# ADC.net
KiCad netlist of a schematic drawn in Altium Designer
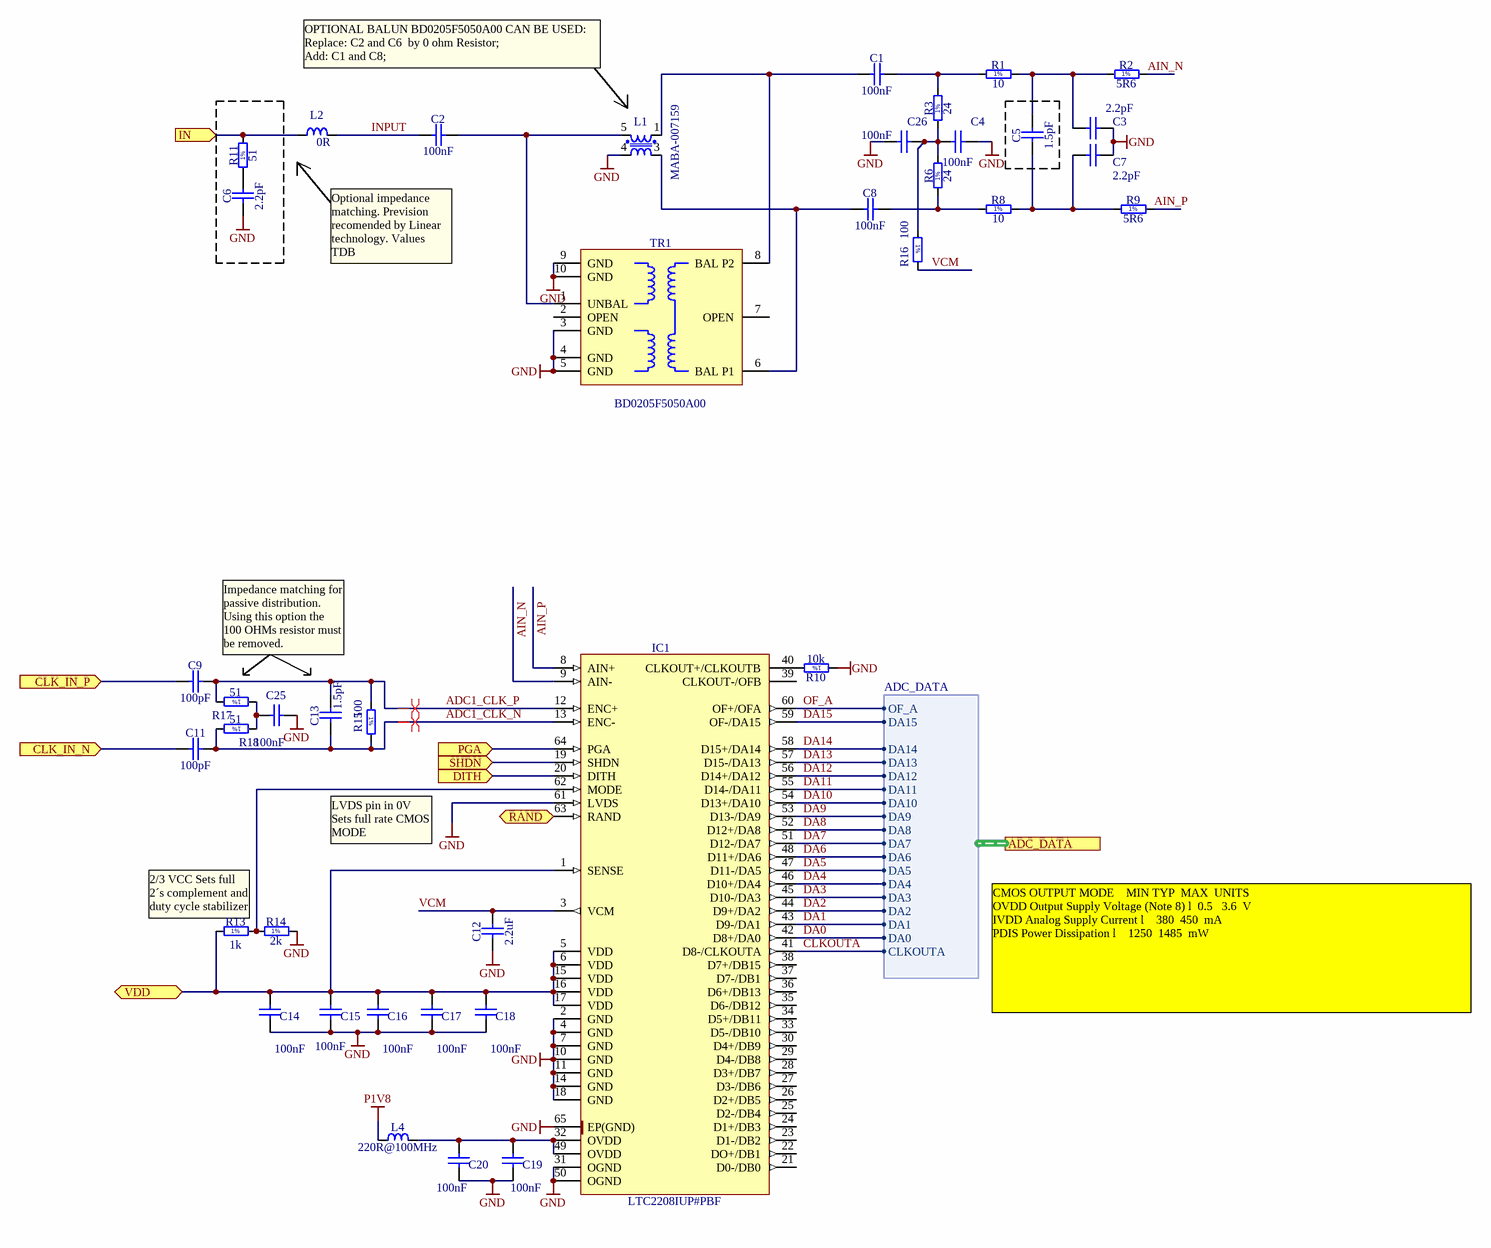
[diagram p0: ADC.SchDoc]

(export (version "E")
  (design (tool "Eeschema 10.0.6"))
  (components
    (comp (ref "C1")
      (value "100nF")
      (footprint "CAPC0603X33N")
      (description "Non-polarised capacitor")
      (fields
        (field (name "PART NUMBER") "CC0201_100NF_6.3V_10%_X5R")
        (field (name "VOLTAGE") "6.3V")
        (field (name "AUTHOR") "CERN DEM JLC")
      )
      (libsource (lib "Capacitors") (part "Capacitor - non polarized"))
    )
    (comp (ref "C2")
      (value "100nF")
      (footprint "CAPC0603X33N")
      (description "Non-polarised capacitor")
      (fields
        (field (name "PART NUMBER") "CC0201_100NF_6.3V_10%_X5R")
        (field (name "VOLTAGE") "6.3V")
        (field (name "AUTHOR") "CERN DEM JLC")
      )
      (libsource (lib "Capacitors") (part "Capacitor - non polarized"))
    )
    (comp (ref "C3")
      (value "2.2pF")
      (footprint "CAPC1005X55N")
      (description "Non-polarised capacitor")
      (fields
        (field (name "PART NUMBER") "CC0402_2.2PF_50V_0.25PF_NP0")
        (field (name "VOLTAGE") "50V")
        (field (name "AUTHOR") "CERN DEM JLC")
      )
      (libsource (lib "Capacitors") (part "Capacitor - non polarized"))
    )
    (comp (ref "C4")
      (value "100nF")
      (footprint "CAPC0603X33N")
      (description "Non-polarised capacitor")
      (fields
        (field (name "PART NUMBER") "CC0201_100NF_6.3V_10%_X5R")
        (field (name "VOLTAGE") "6.3V")
        (field (name "AUTHOR") "CERN DEM JLC")
      )
      (libsource (lib "Capacitors") (part "Capacitor - non polarized"))
    )
    (comp (ref "C5")
      (value "1.5pF")
      (footprint "CAPC1005X55N")
      (description "Non-polarised capacitor")
      (fields
        (field (name "PART NUMBER") "CC0402_1.5PF_50V_0.25PF_NP0")
        (field (name "VOLTAGE") "50V")
        (field (name "AUTHOR") "CERN DEM JLC")
      )
      (libsource (lib "Capacitors") (part "Capacitor - non polarized"))
    )
    (comp (ref "C6")
      (value "2.2pF")
      (footprint "CAPC1005X55N")
      (description "Non-polarised capacitor")
      (fields
        (field (name "PART NUMBER") "CC0402_2.2PF_50V_0.25PF_NP0")
        (field (name "VOLTAGE") "50V")
        (field (name "AUTHOR") "CERN DEM JLC")
      )
      (libsource (lib "Capacitors") (part "Capacitor - non polarized"))
    )
    (comp (ref "C7")
      (value "2.2pF")
      (footprint "CAPC1005X55N")
      (description "Non-polarised capacitor")
      (fields
        (field (name "PART NUMBER") "CC0402_2.2PF_50V_0.25PF_NP0")
        (field (name "VOLTAGE") "50V")
        (field (name "AUTHOR") "CERN DEM JLC")
      )
      (libsource (lib "Capacitors") (part "Capacitor - non polarized"))
    )
    (comp (ref "C8")
      (value "100nF")
      (footprint "CAPC0603X33N")
      (description "Non-polarised capacitor")
      (fields
        (field (name "PART NUMBER") "CC0201_100NF_6.3V_10%_X5R")
        (field (name "VOLTAGE") "6.3V")
        (field (name "AUTHOR") "CERN DEM JLC")
      )
      (libsource (lib "Capacitors") (part "Capacitor - non polarized"))
    )
    (comp (ref "C9")
      (value "100pF")
      (footprint "CAPC1005X55N")
      (description "Non-polarised capacitor")
      (fields
        (field (name "PART NUMBER") "CC0402_100PF_50V_5%_NP0")
        (field (name "VOLTAGE") "50V")
        (field (name "AUTHOR") "CERN DEM JLC")
      )
      (libsource (lib "Capacitors") (part "Capacitor - non polarized"))
    )
    (comp (ref "C11")
      (value "100pF")
      (footprint "CAPC1005X55N")
      (description "Non-polarised capacitor")
      (fields
        (field (name "PART NUMBER") "CC0402_100PF_50V_5%_NP0")
        (field (name "VOLTAGE") "50V")
        (field (name "AUTHOR") "CERN DEM JLC")
      )
      (libsource (lib "Capacitors") (part "Capacitor - non polarized"))
    )
    (comp (ref "C12")
      (value "2.2uF")
      (footprint "CAPC1608X87N")
      (description "Non-polarised capacitor")
      (fields
        (field (name "PART NUMBER") "CC0603_2.2UF_16V_10%_X5R")
        (field (name "VOLTAGE") "16V")
        (field (name "AUTHOR") "CERN DEM JLC")
      )
      (libsource (lib "Capacitors") (part "Capacitor - non polarized"))
    )
    (comp (ref "C13")
      (value "1.5pF")
      (footprint "CAPC1005X55N")
      (description "Non-polarised capacitor")
      (fields
        (field (name "PART NUMBER") "CC0402_1.5PF_50V_0.25PF_NP0")
        (field (name "VOLTAGE") "50V")
        (field (name "AUTHOR") "CERN DEM JLC")
      )
      (libsource (lib "Capacitors") (part "Capacitor - non polarized"))
    )
    (comp (ref "C14")
      (value "100nF")
      (footprint "CAPC0603X33N")
      (description "Non-polarised capacitor")
      (fields
        (field (name "PART NUMBER") "CC0201_100NF_6.3V_10%_X5R")
        (field (name "VOLTAGE") "6.3V")
        (field (name "AUTHOR") "CERN DEM JLC")
      )
      (libsource (lib "Capacitors") (part "Capacitor - non polarized"))
    )
    (comp (ref "C15")
      (value "100nF")
      (footprint "CAPC0603X33N")
      (description "Non-polarised capacitor")
      (fields
        (field (name "PART NUMBER") "CC0201_100NF_6.3V_10%_X5R")
        (field (name "VOLTAGE") "6.3V")
        (field (name "AUTHOR") "CERN DEM JLC")
      )
      (libsource (lib "Capacitors") (part "Capacitor - non polarized"))
    )
    (comp (ref "C16")
      (value "100nF")
      (footprint "CAPC0603X33N")
      (description "Non-polarised capacitor")
      (fields
        (field (name "PART NUMBER") "CC0201_100NF_6.3V_10%_X5R")
        (field (name "VOLTAGE") "6.3V")
        (field (name "AUTHOR") "CERN DEM JLC")
      )
      (libsource (lib "Capacitors") (part "Capacitor - non polarized"))
    )
    (comp (ref "C17")
      (value "100nF")
      (footprint "CAPC0603X33N")
      (description "Non-polarised capacitor")
      (fields
        (field (name "PART NUMBER") "CC0201_100NF_6.3V_10%_X5R")
        (field (name "VOLTAGE") "6.3V")
        (field (name "AUTHOR") "CERN DEM JLC")
      )
      (libsource (lib "Capacitors") (part "Capacitor - non polarized"))
    )
    (comp (ref "C18")
      (value "100nF")
      (footprint "CAPC0603X33N")
      (description "Non-polarised capacitor")
      (fields
        (field (name "PART NUMBER") "CC0201_100NF_6.3V_10%_X5R")
        (field (name "VOLTAGE") "6.3V")
        (field (name "AUTHOR") "CERN DEM JLC")
      )
      (libsource (lib "Capacitors") (part "Capacitor - non polarized"))
    )
    (comp (ref "C19")
      (value "100nF")
      (footprint "CAPC0603X33N")
      (description "Non-polarised capacitor")
      (fields
        (field (name "PART NUMBER") "CC0201_100NF_6.3V_10%_X5R")
        (field (name "VOLTAGE") "6.3V")
        (field (name "AUTHOR") "CERN DEM JLC")
      )
      (libsource (lib "Capacitors") (part "Capacitor - non polarized"))
    )
    (comp (ref "C20")
      (value "100nF")
      (footprint "CAPC0603X33N")
      (description "Non-polarised capacitor")
      (fields
        (field (name "PART NUMBER") "CC0201_100NF_6.3V_10%_X5R")
        (field (name "VOLTAGE") "6.3V")
        (field (name "AUTHOR") "CERN DEM JLC")
      )
      (libsource (lib "Capacitors") (part "Capacitor - non polarized"))
    )
    (comp (ref "C25")
      (value "100nF")
      (footprint "CAPC0603X33N")
      (description "Non-polarised capacitor")
      (fields
        (field (name "PART NUMBER") "CC0201_100NF_6.3V_10%_X5R")
        (field (name "VOLTAGE") "6.3V")
        (field (name "AUTHOR") "CERN DEM JLC")
      )
      (libsource (lib "Capacitors") (part "Capacitor - non polarized"))
    )
    (comp (ref "C26")
      (value "100nF")
      (footprint "CAPC0603X33N")
      (description "Non-polarised capacitor")
      (fields
        (field (name "PART NUMBER") "CC0201_100NF_6.3V_10%_X5R")
        (field (name "VOLTAGE") "6.3V")
        (field (name "AUTHOR") "CERN DEM JLC")
      )
      (libsource (lib "Capacitors") (part "Capacitor - non polarized"))
    )
    (comp (ref "IC1")
      (value "LTC2208IUP#PBF")
      (footprint "QFN50P900X900X80-65N-S725")
      (description "16-Bit, 130Msps ADC")
      (fields
        (field (name "PART NUMBER") "LTC2LTC2208IUP#PBF")
        (field (name "MANUFACTURER") "LINEAR TECHNOLOGY")
        (field (name "AUTHOR") "CERN DEM JLC")
      )
      (libsource (lib "ICs And Semiconductors") (part "LTC2208"))
    )
    (comp (ref "L1")
      (value "MABA-007159")
      (footprint "XFMR_MA-COM_SM-22 (H260)")
      (description "MA-COM E-Serie RF 1:1 Transmission Line Ttransformer 4.5-3000MHz")
      (libsource (lib "fmclib") (part "XFMR_MA-COM_MABA-007159-000000_modified"))
    )
    (comp (ref "L2")
      (value "0R")
      (footprint "INDC1005X55N")
      (description "Inductor")
      (fields
        (field (name "PART NUMBER") "IND0402_MURATA_BLM15HB221SN1")
        (field (name "POWER") "250mA")
        (field (name "AUTHOR") "CERN DEM JLC")
      )
      (libsource (lib "Inductors & Transformers") (part "Inductor"))
    )
    (comp (ref "L4")
      (value "220R@100MHz")
      (footprint "INDC2012X105N")
      (description "Inductor")
      (fields
        (field (name "PART NUMBER") "IND0805_MURATA_BLM21PG221SN1D")
        (field (name "POWER") "2A")
        (field (name "AUTHOR") "CERN DEM JLC")
      )
      (libsource (lib "Inductors & Transformers") (part "Inductor"))
    )
    (comp (ref "R1")
      (value "10")
      (footprint "RESC1005X40N")
      (description "Resistor - 1%")
      (fields
        (field (name "PART NUMBER") "R0402_10R_1%_0.0625W_200PPM")
        (field (name "POWER") "0.0625W")
        (field (name "AUTHOR") "CERN DEM JLC")
      )
      (libsource (lib "Resistors") (part "Resistor - 1%"))
    )
    (comp (ref "R2")
      (value "5R6")
      (footprint "RESC1005X40N")
      (description "Resistor - 1%")
      (fields
        (field (name "PART NUMBER") "R0402_5R6_1%_0.0625W_200PPM")
        (field (name "POWER") "0.0625W")
        (field (name "AUTHOR") "CERN DEM JLC")
      )
      (libsource (lib "Resistors") (part "Resistor - 1%"))
    )
    (comp (ref "R3")
      (value "24")
      (footprint "RESC1005X40N")
      (description "Resistor - 1%")
      (fields
        (field (name "PART NUMBER") "R0402_24R_1%_0.0625W_100PPM")
        (field (name "POWER") "0.0625W")
        (field (name "AUTHOR") "CERN DEM JLC")
      )
      (libsource (lib "Resistors") (part "Resistor - 1%"))
    )
    (comp (ref "R6")
      (value "24")
      (footprint "RESC1005X40N")
      (description "Resistor - 1%")
      (fields
        (field (name "PART NUMBER") "R0402_24R_1%_0.0625W_100PPM")
        (field (name "POWER") "0.0625W")
        (field (name "AUTHOR") "CERN DEM JLC")
      )
      (libsource (lib "Resistors") (part "Resistor - 1%"))
    )
    (comp (ref "R8")
      (value "10")
      (footprint "RESC1005X40N")
      (description "Resistor - 1%")
      (fields
        (field (name "PART NUMBER") "R0402_10R_1%_0.0625W_200PPM")
        (field (name "POWER") "0.0625W")
        (field (name "AUTHOR") "CERN DEM JLC")
      )
      (libsource (lib "Resistors") (part "Resistor - 1%"))
    )
    (comp (ref "R9")
      (value "5R6")
      (footprint "RESC1005X40N")
      (description "Resistor - 1%")
      (fields
        (field (name "PART NUMBER") "R0402_5R6_1%_0.0625W_200PPM")
        (field (name "POWER") "0.0625W")
        (field (name "AUTHOR") "CERN DEM JLC")
      )
      (libsource (lib "Resistors") (part "Resistor - 1%"))
    )
    (comp (ref "R10")
      (value "10k")
      (footprint "RESC1005X40N")
      (description "Resistor - 1%")
      (fields
        (field (name "PART NUMBER") "R0402_10K_1%_0.0625W_100PPM")
        (field (name "POWER") "0.0625W")
        (field (name "AUTHOR") "CERN DEM JLC")
      )
      (libsource (lib "Resistors") (part "Resistor - 1%"))
    )
    (comp (ref "R11")
      (value "51")
      (footprint "RESC1005X40N")
      (description "Resistor - 1%")
      (fields
        (field (name "PART NUMBER") "R0402_51R_1%_0.0625W_100PPM")
        (field (name "POWER") "0.0625W")
        (field (name "AUTHOR") "CERN DEM JLC")
      )
      (libsource (lib "Resistors") (part "Resistor - 1%"))
    )
    (comp (ref "R13")
      (value "1k")
      (footprint "RESC1005X40N")
      (description "Resistor - 1%")
      (fields
        (field (name "PART NUMBER") "R0402_1K_1%_0.0625W_100PPM")
        (field (name "POWER") "0.0625W")
        (field (name "AUTHOR") "CERN DEM JLC")
      )
      (libsource (lib "Resistors") (part "Resistor - 1%"))
    )
    (comp (ref "R14")
      (value "2k")
      (footprint "RESC1005X40N")
      (description "Resistor - 1%")
      (fields
        (field (name "PART NUMBER") "R0402_2K_1%_0.0625W_100PPM")
        (field (name "POWER") "0.0625W")
        (field (name "AUTHOR") "CERN DEM JLC")
      )
      (libsource (lib "Resistors") (part "Resistor - 1%"))
    )
    (comp (ref "R15")
      (value "100")
      (footprint "RESC1005X40N")
      (description "Resistor - 1%")
      (fields
        (field (name "PART NUMBER") "R0402_100R_1%_0.0625W_100PPM")
        (field (name "POWER") "0.0625W")
        (field (name "AUTHOR") "CERN DEM JLC")
      )
      (libsource (lib "Resistors") (part "Resistor - 1%"))
    )
    (comp (ref "R16")
      (value "100")
      (footprint "RESC1005X40N")
      (description "Resistor - 1%")
      (fields
        (field (name "PART NUMBER") "R0402_100R_1%_0.0625W_100PPM")
        (field (name "POWER") "0.0625W")
        (field (name "AUTHOR") "CERN DEM JLC")
      )
      (libsource (lib "Resistors") (part "Resistor - 1%"))
    )
    (comp (ref "R17")
      (value "51")
      (footprint "RESC1005X40N")
      (description "Resistor - 1%")
      (fields
        (field (name "PART NUMBER") "R0402_51R_1%_0.0625W_100PPM")
        (field (name "POWER") "0.0625W")
        (field (name "AUTHOR") "CERN DEM JLC")
      )
      (libsource (lib "Resistors") (part "Resistor - 1%"))
    )
    (comp (ref "R18")
      (value "51")
      (footprint "RESC1005X40N")
      (description "Resistor - 1%")
      (fields
        (field (name "PART NUMBER") "R0402_51R_1%_0.0625W_100PPM")
        (field (name "POWER") "0.0625W")
        (field (name "AUTHOR") "CERN DEM JLC")
      )
      (libsource (lib "Resistors") (part "Resistor - 1%"))
    )
    (comp (ref "TR1")
      (value "BD0205F5050A00")
      (footprint "XFMR_ANAREN_BD0205F5050A00")
      (description "70MHz - 1000MHz Ultra Low Profile Sub-Miniature Balanced to Unbalanced Transformer")
      (fields
        (field (name "PART NUMBER") "XFMR_ANAREN_BD0205F5050A00")
        (field (name "MANUFACTURER") "ANAREN")
        (field (name "MANUFACTURER PART NUMBER") "BD0205F5050A00")
        (field (name "AUTHOR") "CERN DEM JLC")
      )
      (libsource (lib "Inductors & Transformers") (part "XFMR_ANAREN_BD0205F5050A00"))
    )
  )
  (nets
    (net (code "2") (name "/ADC1_CLK_N") (class "Default")
      (node (ref "C11") (pin "2") (pinfunction "2_2") (pintype "passive"))
      (node (ref "C13") (pin "1") (pinfunction "1_1") (pintype "passive"))
      (node (ref "IC1") (pin "13") (pinfunction "ENC-_13") (pintype "input"))
      (node (ref "R15") (pin "2") (pinfunction "2_2") (pintype "passive"))
      (node (ref "R18") (pin "2") (pinfunction "2_2") (pintype "passive"))
    )
    (net (code "3") (name "/ADC1_CLK_P") (class "Default")
      (node (ref "C13") (pin "2") (pinfunction "2_2") (pintype "passive"))
      (node (ref "C9") (pin "2") (pinfunction "2_2") (pintype "passive"))
      (node (ref "IC1") (pin "12") (pinfunction "ENC+_12") (pintype "input"))
      (node (ref "R15") (pin "1") (pinfunction "1_1") (pintype "passive"))
      (node (ref "R17") (pin "2") (pinfunction "2_2") (pintype "passive"))
    )
    (net (code "4") (name "/AIN_N") (class "Default")
      (node (ref "IC1") (pin "9") (pinfunction "AIN-_9") (pintype "input"))
      (node (ref "R2") (pin "2") (pinfunction "2_2") (pintype "passive"))
    )
    (net (code "5") (name "/AIN_P") (class "Default")
      (node (ref "IC1") (pin "8") (pinfunction "AIN+_8") (pintype "input"))
      (node (ref "R9") (pin "2") (pinfunction "2_2") (pintype "passive"))
    )
    (net (code "6") (name "/CLKOUTA") (class "Default")
      (node (ref "IC1") (pin "41") (pinfunction "D8-/CLKOUTA_41") (pintype "output"))
    )
    (net (code "7") (name "/CLK_IN_N") (class "Default")
      (node (ref "C11") (pin "1") (pinfunction "1_1") (pintype "passive"))
    )
    (net (code "8") (name "/CLK_IN_P") (class "Default")
      (node (ref "C9") (pin "1") (pinfunction "1_1") (pintype "passive"))
    )
    (net (code "9") (name "/DA0") (class "Default")
      (node (ref "IC1") (pin "42") (pinfunction "D8+/DA0_42") (pintype "output"))
    )
    (net (code "10") (name "/DA1") (class "Default")
      (node (ref "IC1") (pin "43") (pinfunction "D9-/DA1_43") (pintype "output"))
    )
    (net (code "11") (name "/DA2") (class "Default")
      (node (ref "IC1") (pin "44") (pinfunction "D9+/DA2_44") (pintype "output"))
    )
    (net (code "12") (name "/DA3") (class "Default")
      (node (ref "IC1") (pin "45") (pinfunction "D10-/DA3_45") (pintype "output"))
    )
    (net (code "13") (name "/DA4") (class "Default")
      (node (ref "IC1") (pin "46") (pinfunction "D10+/DA4_46") (pintype "output"))
    )
    (net (code "14") (name "/DA5") (class "Default")
      (node (ref "IC1") (pin "47") (pinfunction "D11-/DA5_47") (pintype "output"))
    )
    (net (code "15") (name "/DA6") (class "Default")
      (node (ref "IC1") (pin "48") (pinfunction "D11+/DA6_48") (pintype "output"))
    )
    (net (code "16") (name "/DA7") (class "Default")
      (node (ref "IC1") (pin "51") (pinfunction "D12-/DA7_51") (pintype "output"))
    )
    (net (code "17") (name "/DA8") (class "Default")
      (node (ref "IC1") (pin "52") (pinfunction "D12+/DA8_52") (pintype "output"))
    )
    (net (code "18") (name "/DA9") (class "Default")
      (node (ref "IC1") (pin "53") (pinfunction "D13-/DA9_53") (pintype "output"))
    )
    (net (code "19") (name "/DA10") (class "Default")
      (node (ref "IC1") (pin "54") (pinfunction "D13+/DA10_54") (pintype "output"))
    )
    (net (code "20") (name "/DA11") (class "Default")
      (node (ref "IC1") (pin "55") (pinfunction "D14-/DA11_55") (pintype "output"))
    )
    (net (code "21") (name "/DA12") (class "Default")
      (node (ref "IC1") (pin "56") (pinfunction "D14+/DA12_56") (pintype "output"))
    )
    (net (code "22") (name "/DA13") (class "Default")
      (node (ref "IC1") (pin "57") (pinfunction "D15-/DA13_57") (pintype "output"))
    )
    (net (code "23") (name "/DA14") (class "Default")
      (node (ref "IC1") (pin "58") (pinfunction "D15+/DA14_58") (pintype "output"))
    )
    (net (code "24") (name "/DA15") (class "Default")
      (node (ref "IC1") (pin "59") (pinfunction "OF-/DA15_59") (pintype "output"))
    )
    (net (code "25") (name "/DITH") (class "Default")
      (node (ref "IC1") (pin "20") (pinfunction "DITH_20") (pintype "input"))
    )
    (net (code "26") (name "/IN") (class "Default")
      (node (ref "L2") (pin "1") (pinfunction "1_1") (pintype "passive"))
      (node (ref "R11") (pin "2") (pinfunction "2_2") (pintype "passive"))
    )
    (net (code "27") (name "/INPUT") (class "Default")
      (node (ref "C2") (pin "1") (pinfunction "1_1") (pintype "passive"))
      (node (ref "L2") (pin "2") (pinfunction "2_2") (pintype "passive"))
    )
    (net (code "28") (name "/OF_A") (class "Default")
      (node (ref "IC1") (pin "60") (pinfunction "OF+/OFA_60") (pintype "output"))
    )
    (net (code "29") (name "/PGA") (class "Default")
      (node (ref "IC1") (pin "64") (pinfunction "PGA_64") (pintype "input"))
    )
    (net (code "30") (name "/RAND") (class "Default")
      (node (ref "IC1") (pin "63") (pinfunction "RAND_63") (pintype "input"))
    )
    (net (code "31") (name "/SHDN") (class "Default")
      (node (ref "IC1") (pin "19") (pinfunction "SHDN_19") (pintype "input"))
    )
    (net (code "32") (name "/VCM") (class "Default")
      (node (ref "C12") (pin "2") (pinfunction "2_2") (pintype "passive"))
      (node (ref "IC1") (pin "3") (pinfunction "VCM_3") (pintype "output"))
      (node (ref "R16") (pin "2") (pinfunction "2_2") (pintype "passive"))
    )
    (net (code "33") (name "/VDD") (class "Default")
      (node (ref "C14") (pin "2") (pinfunction "2_2") (pintype "passive"))
      (node (ref "C15") (pin "2") (pinfunction "2_2") (pintype "passive"))
      (node (ref "C16") (pin "2") (pinfunction "2_2") (pintype "passive"))
      (node (ref "C17") (pin "2") (pinfunction "2_2") (pintype "passive"))
      (node (ref "C18") (pin "2") (pinfunction "2_2") (pintype "passive"))
      (node (ref "IC1") (pin "1") (pinfunction "SENSE_1") (pintype "input"))
      (node (ref "IC1") (pin "15") (pinfunction "VDD_15") (pintype "power_in"))
      (node (ref "IC1") (pin "16") (pinfunction "VDD_16") (pintype "power_in"))
      (node (ref "IC1") (pin "17") (pinfunction "VDD_17") (pintype "power_in"))
      (node (ref "IC1") (pin "5") (pinfunction "VDD_5") (pintype "power_in"))
      (node (ref "IC1") (pin "6") (pinfunction "VDD_6") (pintype "power_in"))
      (node (ref "R13") (pin "1") (pinfunction "1_1") (pintype "passive"))
    )
    (net (code "35") (name "GND") (class "Default")
      (node (ref "C12") (pin "1") (pinfunction "1_1") (pintype "passive"))
      (node (ref "C14") (pin "1") (pinfunction "1_1") (pintype "passive"))
      (node (ref "C15") (pin "1") (pinfunction "1_1") (pintype "passive"))
      (node (ref "C16") (pin "1") (pinfunction "1_1") (pintype "passive"))
      (node (ref "C17") (pin "1") (pinfunction "1_1") (pintype "passive"))
      (node (ref "C18") (pin "1") (pinfunction "1_1") (pintype "passive"))
      (node (ref "C19") (pin "1") (pinfunction "1_1") (pintype "passive"))
      (node (ref "C20") (pin "1") (pinfunction "1_1") (pintype "passive"))
      (node (ref "C25") (pin "1") (pinfunction "1_1") (pintype "passive"))
      (node (ref "C26") (pin "2") (pinfunction "2_2") (pintype "passive"))
      (node (ref "C3") (pin "2") (pinfunction "2_2") (pintype "passive"))
      (node (ref "C4") (pin "2") (pinfunction "2_2") (pintype "passive"))
      (node (ref "C6") (pin "1") (pinfunction "1_1") (pintype "passive"))
      (node (ref "C7") (pin "2") (pinfunction "2_2") (pintype "passive"))
      (node (ref "IC1") (pin "10") (pinfunction "GND_10") (pintype "power_in"))
      (node (ref "IC1") (pin "11") (pinfunction "GND_11") (pintype "power_in"))
      (node (ref "IC1") (pin "14") (pinfunction "GND_14") (pintype "power_in"))
      (node (ref "IC1") (pin "18") (pinfunction "GND_18") (pintype "power_in"))
      (node (ref "IC1") (pin "2") (pinfunction "GND_2") (pintype "power_in"))
      (node (ref "IC1") (pin "31") (pinfunction "OGND_31") (pintype "power_in"))
      (node (ref "IC1") (pin "4") (pinfunction "GND_4") (pintype "power_in"))
      (node (ref "IC1") (pin "50") (pinfunction "OGND_50") (pintype "power_in"))
      (node (ref "IC1") (pin "61") (pinfunction "LVDS_61") (pintype "input"))
      (node (ref "IC1") (pin "65") (pinfunction "EP(GND)_65") (pintype "power_in"))
      (node (ref "IC1") (pin "7") (pinfunction "GND_7") (pintype "power_in"))
      (node (ref "L1") (pin "4") (pinfunction "4_4") (pintype "passive"))
      (node (ref "R10") (pin "1") (pinfunction "1_1") (pintype "passive"))
      (node (ref "R14") (pin "2") (pinfunction "2_2") (pintype "passive"))
      (node (ref "TR1") (pin "10") (pinfunction "GND_10") (pintype "power_in"))
      (node (ref "TR1") (pin "3") (pinfunction "GND_3") (pintype "power_in"))
      (node (ref "TR1") (pin "4") (pinfunction "GND_4") (pintype "power_in"))
      (node (ref "TR1") (pin "5") (pinfunction "GND_5") (pintype "power_in"))
      (node (ref "TR1") (pin "9") (pinfunction "GND_9") (pintype "power_in"))
    )
    (net (code "36") (name "Net-(C1-Pad2)") (class "Default")
      (node (ref "C1") (pin "2") (pinfunction "2_2") (pintype "passive"))
      (node (ref "R1") (pin "1") (pinfunction "1_1") (pintype "passive"))
      (node (ref "R3") (pin "2") (pinfunction "2_2") (pintype "passive"))
    )
    (net (code "37") (name "Net-(C3-Pad1)") (class "Default")
      (node (ref "C3") (pin "1") (pinfunction "1_1") (pintype "passive"))
      (node (ref "C5") (pin "2") (pinfunction "2_2") (pintype "passive"))
      (node (ref "R1") (pin "2") (pinfunction "2_2") (pintype "passive"))
      (node (ref "R2") (pin "1") (pinfunction "1_1") (pintype "passive"))
    )
    (net (code "38") (name "Net-(C5-Pad1)") (class "Default")
      (node (ref "C5") (pin "1") (pinfunction "1_1") (pintype "passive"))
      (node (ref "C7") (pin "1") (pinfunction "1_1") (pintype "passive"))
      (node (ref "R8") (pin "2") (pinfunction "2_2") (pintype "passive"))
      (node (ref "R9") (pin "1") (pinfunction "1_1") (pintype "passive"))
    )
    (net (code "39") (name "Net-(C6-Pad2)") (class "Default")
      (node (ref "C6") (pin "2") (pinfunction "2_2") (pintype "passive"))
      (node (ref "R11") (pin "1") (pinfunction "1_1") (pintype "passive"))
    )
    (net (code "40") (name "Net-(C8-Pad2)") (class "Default")
      (node (ref "C8") (pin "2") (pinfunction "2_2") (pintype "passive"))
      (node (ref "R6") (pin "1") (pinfunction "1_1") (pintype "passive"))
      (node (ref "R8") (pin "1") (pinfunction "1_1") (pintype "passive"))
    )
    (net (code "41") (name "Net-(C19-Pad2)") (class "Default")
      (node (ref "C19") (pin "2") (pinfunction "2_2") (pintype "passive"))
      (node (ref "C20") (pin "2") (pinfunction "2_2") (pintype "passive"))
      (node (ref "IC1") (pin "32") (pinfunction "OVDD_32") (pintype "power_in"))
      (node (ref "IC1") (pin "49") (pinfunction "OVDD_49") (pintype "power_in"))
      (node (ref "L4") (pin "2") (pinfunction "2_2") (pintype "passive"))
    )
    (net (code "42") (name "Net-(C25-Pad2)") (class "Default")
      (node (ref "C25") (pin "2") (pinfunction "2_2") (pintype "passive"))
      (node (ref "R17") (pin "1") (pinfunction "1_1") (pintype "passive"))
      (node (ref "R18") (pin "1") (pinfunction "1_1") (pintype "passive"))
    )
    (net (code "43") (name "Net-(C26-Pad1)") (class "Default")
      (node (ref "C26") (pin "1") (pinfunction "1_1") (pintype "passive"))
      (node (ref "C4") (pin "1") (pinfunction "1_1") (pintype "passive"))
      (node (ref "R16") (pin "1") (pinfunction "1_1") (pintype "passive"))
      (node (ref "R3") (pin "1") (pinfunction "1_1") (pintype "passive"))
      (node (ref "R6") (pin "2") (pinfunction "2_2") (pintype "passive"))
    )
    (net (code "44") (name "Net-(IC1-CLKOUT+{slash}CLKOUTB)") (class "Default")
      (node (ref "IC1") (pin "40") (pinfunction "CLKOUT+/CLKOUTB_40") (pintype "power_in"))
      (node (ref "R10") (pin "2") (pinfunction "2_2") (pintype "passive"))
    )
    (net (code "45") (name "Net-(IC1-MODE)") (class "Default")
      (node (ref "IC1") (pin "62") (pinfunction "MODE_62") (pintype "input"))
      (node (ref "R13") (pin "2") (pinfunction "2_2") (pintype "passive"))
      (node (ref "R14") (pin "1") (pinfunction "1_1") (pintype "passive"))
    )
    (net (code "46") (name "Net-(TR1-BAL_P1)") (class "Default")
      (node (ref "C8") (pin "1") (pinfunction "1_1") (pintype "passive"))
      (node (ref "L1") (pin "3") (pinfunction "3_3") (pintype "passive"))
      (node (ref "TR1") (pin "6") (pinfunction "BAL_P1_6") (pintype "passive"))
    )
    (net (code "47") (name "Net-(TR1-BAL_P2)") (class "Default")
      (node (ref "C1") (pin "1") (pinfunction "1_1") (pintype "passive"))
      (node (ref "L1") (pin "1") (pinfunction "1_1") (pintype "passive"))
      (node (ref "TR1") (pin "8") (pinfunction "BAL_P2_8") (pintype "passive"))
    )
    (net (code "48") (name "Net-(TR1-UNBAL)") (class "Default")
      (node (ref "C2") (pin "2") (pinfunction "2_2") (pintype "passive"))
      (node (ref "L1") (pin "5") (pinfunction "5_5") (pintype "passive"))
      (node (ref "TR1") (pin "1") (pinfunction "UNBAL_1") (pintype "passive"))
    )
    (net (code "49") (name "P1V8") (class "Default")
      (node (ref "L4") (pin "1") (pinfunction "1_1") (pintype "passive"))
    )
    (net (code "50") (name "unconnected-(IC1-CLKOUT-{slash}OFB-Pad39)") (class "Default")
      (node (ref "IC1") (pin "39") (pinfunction "CLKOUT-/OFB_39") (pintype "power_in"))
    )
    (net (code "51") (name "unconnected-(IC1-D0-{slash}DB0-Pad21)") (class "Default")
      (node (ref "IC1") (pin "21") (pinfunction "D0-/DB0_21") (pintype "output"))
    )
    (net (code "52") (name "unconnected-(IC1-D1+{slash}DB3-Pad24)") (class "Default")
      (node (ref "IC1") (pin "24") (pinfunction "D1+/DB3_24") (pintype "output"))
    )
    (net (code "53") (name "unconnected-(IC1-D1-{slash}DB2-Pad23)") (class "Default")
      (node (ref "IC1") (pin "23") (pinfunction "D1-/DB2_23") (pintype "output"))
    )
    (net (code "54") (name "unconnected-(IC1-D2+{slash}DB5-Pad26)") (class "Default")
      (node (ref "IC1") (pin "26") (pinfunction "D2+/DB5_26") (pintype "output"))
    )
    (net (code "55") (name "unconnected-(IC1-D2-{slash}DB4-Pad25)") (class "Default")
      (node (ref "IC1") (pin "25") (pinfunction "D2-/DB4_25") (pintype "output"))
    )
    (net (code "56") (name "unconnected-(IC1-D3+{slash}DB7-Pad28)") (class "Default")
      (node (ref "IC1") (pin "28") (pinfunction "D3+/DB7_28") (pintype "output"))
    )
    (net (code "57") (name "unconnected-(IC1-D3-{slash}DB6-Pad27)") (class "Default")
      (node (ref "IC1") (pin "27") (pinfunction "D3-/DB6_27") (pintype "output"))
    )
    (net (code "58") (name "unconnected-(IC1-D4+{slash}DB9-Pad30)") (class "Default")
      (node (ref "IC1") (pin "30") (pinfunction "D4+/DB9_30") (pintype "output"))
    )
    (net (code "59") (name "unconnected-(IC1-D4-{slash}DB8-Pad29)") (class "Default")
      (node (ref "IC1") (pin "29") (pinfunction "D4-/DB8_29") (pintype "output"))
    )
    (net (code "60") (name "unconnected-(IC1-D5+{slash}DB11-Pad34)") (class "Default")
      (node (ref "IC1") (pin "34") (pinfunction "D5+/DB11_34") (pintype "output"))
    )
    (net (code "61") (name "unconnected-(IC1-D5-{slash}DB10-Pad33)") (class "Default")
      (node (ref "IC1") (pin "33") (pinfunction "D5-/DB10_33") (pintype "output"))
    )
    (net (code "62") (name "unconnected-(IC1-D6+{slash}DB13-Pad36)") (class "Default")
      (node (ref "IC1") (pin "36") (pinfunction "D6+/DB13_36") (pintype "output"))
    )
    (net (code "63") (name "unconnected-(IC1-D6-{slash}DB12-Pad35)") (class "Default")
      (node (ref "IC1") (pin "35") (pinfunction "D6-/DB12_35") (pintype "output"))
    )
    (net (code "64") (name "unconnected-(IC1-D7+{slash}DB15-Pad38)") (class "Default")
      (node (ref "IC1") (pin "38") (pinfunction "D7+/DB15_38") (pintype "output"))
    )
    (net (code "65") (name "unconnected-(IC1-D7-{slash}DB1-Pad37)") (class "Default")
      (node (ref "IC1") (pin "37") (pinfunction "D7-/DB1_37") (pintype "output"))
    )
    (net (code "66") (name "unconnected-(IC1-DO+{slash}DB1-Pad22)") (class "Default")
      (node (ref "IC1") (pin "22") (pinfunction "DO+/DB1_22") (pintype "output"))
    )
    (net (code "67") (name "unconnected-(TR1-OPEN-Pad2)") (class "Default")
      (node (ref "TR1") (pin "2") (pinfunction "OPEN_2") (pintype "passive"))
    )
    (net (code "68") (name "unconnected-(TR1-OPEN-Pad7)") (class "Default")
      (node (ref "TR1") (pin "7") (pinfunction "OPEN_7") (pintype "passive"))
    )
  )
)
